# MCU.net
KiCad netlist of a schematic drawn in Altium Designer
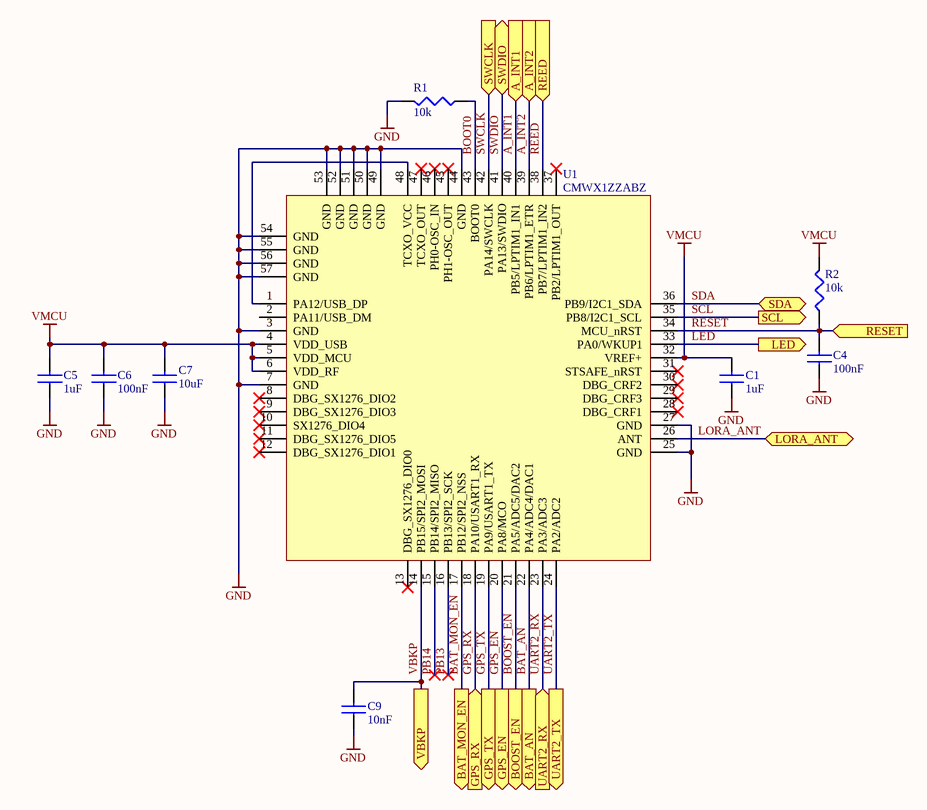
[diagram p0: MCU.SchDoc]

(export (version "E")
  (design (tool "Eeschema 10.0.6"))
  (components
    (comp (ref "C1")
      (value "1uF")
      (footprint "CAP0402")
      (description "CAP CER 1UF 10V 20% X5R 0402")
      (fields
        (field (name "MANUFACTURER") "Murata")
        (field (name "MANUFACTURER PART NUMBER") "GRM155R61A105ME15D")
      )
      (libsource (lib "Passive") (part "C - 1uF/0402"))
    )
    (comp (ref "C4")
      (value "100nF")
      (footprint "CAP0402")
      (fields
        (field (name "MANUFACTURER") "Multicomp")
        (field (name "MANUFACTURER PART NUMBER") "MC0402X104J160CT")
        (field (name "TOLERANCE") "5%")
      )
      (libsource (lib "Passive") (part "C - 100nF/0402"))
    )
    (comp (ref "C5")
      (value "1uF")
      (footprint "CAP0402")
      (description "CAP CER 1UF 10V 20% X5R 0402")
      (fields
        (field (name "MANUFACTURER") "Murata")
        (field (name "MANUFACTURER PART NUMBER") "GRM155R61A105ME15D")
      )
      (libsource (lib "Passive") (part "C - 1uF/0402"))
    )
    (comp (ref "C6")
      (value "100nF")
      (footprint "CAP0402")
      (fields
        (field (name "MANUFACTURER") "Multicomp")
        (field (name "MANUFACTURER PART NUMBER") "MC0402X104J160CT")
        (field (name "TOLERANCE") "5%")
      )
      (libsource (lib "Passive") (part "C - 100nF/0402"))
    )
    (comp (ref "C7")
      (value "10uF")
      (footprint "CAP0603")
      (description "10uf/0603/20%")
      (fields
        (field (name "MANUFACTURER") "KEMET")
        (field (name "MANUFACTURER PART NUMBER") "C0603C106M8PACTU")
      )
      (libsource (lib "pira-smart-schlib") (part "10uF"))
    )
    (comp (ref "C9")
      (value "10nF")
      (footprint "CAP0402")
      (description "CAP CER 10000PF 16V X7R 0402")
      (fields
        (field (name "MANUFACTURER") "Murata")
        (field (name "MANUFACTURER PART NUMBER") "GRM155R71C103KA01D")
      )
      (libsource (lib "Passive") (part "C - 10nF/0402"))
    )
    (comp (ref "R1")
      (value "10k")
      (footprint "RES0402")
      (fields
        (field (name "MANUFACTURER") "Multicomp")
        (field (name "MANUFACTURER PART NUMBER") "MCWR04X1002FTL")
        (field (name "TOLERANCE") "1%")
      )
      (libsource (lib "Passive") (part "R - 10k/0402"))
    )
    (comp (ref "R2")
      (value "10k")
      (footprint "RES0402")
      (fields
        (field (name "MANUFACTURER") "Multicomp")
        (field (name "MANUFACTURER PART NUMBER") "MCWR04X1002FTL")
        (field (name "TOLERANCE") "1%")
      )
      (libsource (lib "Passive") (part "R - 10k/0402"))
    )
    (comp (ref "U1")
      (value "CMWX1ZZABZ")
      (footprint "Lora Module ES0")
      (description "RF Module, FSK, OOK, LoRa, 4.8Kbps, 915MHz, -135.5dBm, 2.2V to 3.6V, I2C, SPI, UART, USB")
      (fields
        (field (name "MANUFACTURER") "Murata")
        (field (name "MANUFACTURER PART NUMBER") "CMWX1ZZABZ-091")
      )
      (libsource (lib "Active") (part "MCU - CMWX1ZZABZ"))
    )
  )
  (nets
    (net (code "1") (name "/A_INT1") (class "Default")
      (node (ref "U1") (pin "40") (pinfunction "PB5/LPTIM1_IN1_40") (pintype "passive"))
    )
    (net (code "2") (name "/A_INT2") (class "Default")
      (node (ref "U1") (pin "39") (pinfunction "PB6/LPTIM1_ETR_39") (pintype "passive"))
    )
    (net (code "3") (name "/BAT_AN") (class "Default")
      (node (ref "U1") (pin "22") (pinfunction "PA4/ADC4/DAC1_22") (pintype "passive"))
    )
    (net (code "4") (name "/BAT_MON_EN") (class "Default")
      (node (ref "U1") (pin "17") (pinfunction "PB12/SPI2_NSS_17") (pintype "passive"))
    )
    (net (code "5") (name "/BOOST_EN") (class "Default")
      (node (ref "U1") (pin "21") (pinfunction "PA5/ADC5/DAC2_21") (pintype "passive"))
    )
    (net (code "6") (name "/BOOT0") (class "Default")
      (node (ref "R1") (pin "1") (pinfunction "1_1") (pintype "passive"))
      (node (ref "U1") (pin "43") (pinfunction "BOOT0_43") (pintype "passive"))
    )
    (net (code "7") (name "/GPS_EN") (class "Default")
      (node (ref "U1") (pin "20") (pinfunction "PA8/MCO_20") (pintype "passive"))
    )
    (net (code "8") (name "/GPS_RX") (class "Default")
      (node (ref "U1") (pin "18") (pinfunction "PA10/USART1_RX_18") (pintype "passive"))
    )
    (net (code "9") (name "/GPS_TX") (class "Default")
      (node (ref "U1") (pin "19") (pinfunction "PA9/USART1_TX_19") (pintype "passive"))
    )
    (net (code "10") (name "/LED") (class "Default")
      (node (ref "U1") (pin "33") (pinfunction "PA0/WKUP1_33") (pintype "passive"))
    )
    (net (code "11") (name "/LORA_ANT") (class "Default")
      (node (ref "U1") (pin "26") (pinfunction "ANT_26") (pintype "passive"))
    )
    (net (code "12") (name "/PB13") (class "Default")
      (node (ref "U1") (pin "16") (pinfunction "PB13/SPI2_SCK_16") (pintype "passive+no_connect"))
    )
    (net (code "13") (name "/PB14") (class "Default")
      (node (ref "U1") (pin "15") (pinfunction "PB14/SPI2_MISO_15") (pintype "passive+no_connect"))
    )
    (net (code "14") (name "/REED") (class "Default")
      (node (ref "U1") (pin "38") (pinfunction "PB7/LPTIM1_IN2_38") (pintype "passive"))
    )
    (net (code "15") (name "/RESET") (class "Default")
      (node (ref "C4") (pin "2") (pinfunction "2_2") (pintype "passive"))
      (node (ref "R2") (pin "1") (pinfunction "1_1") (pintype "passive"))
      (node (ref "U1") (pin "34") (pinfunction "MCU_nRST_34") (pintype "passive"))
    )
    (net (code "16") (name "/SCL") (class "Default")
      (node (ref "U1") (pin "35") (pinfunction "PB8/I2C1_SCL_35") (pintype "passive"))
    )
    (net (code "17") (name "/SDA") (class "Default")
      (node (ref "U1") (pin "36") (pinfunction "PB9/I2C1_SDA_36") (pintype "passive"))
    )
    (net (code "18") (name "/SWCLK") (class "Default")
      (node (ref "U1") (pin "42") (pinfunction "PA14/SWCLK_42") (pintype "passive"))
    )
    (net (code "19") (name "/SWDIO") (class "Default")
      (node (ref "U1") (pin "41") (pinfunction "PA13/SWDIO_41") (pintype "passive"))
    )
    (net (code "20") (name "/UART2_RX") (class "Default")
      (node (ref "U1") (pin "23") (pinfunction "PA3/ADC3_23") (pintype "passive"))
    )
    (net (code "21") (name "/UART2_TX") (class "Default")
      (node (ref "U1") (pin "24") (pinfunction "PA2/ADC2_24") (pintype "passive"))
    )
    (net (code "22") (name "/VBKP") (class "Default")
      (node (ref "C9") (pin "2") (pinfunction "2_2") (pintype "passive"))
      (node (ref "U1") (pin "14") (pinfunction "PB15/SPI2_MOSI_14") (pintype "passive"))
    )
    (net (code "23") (name "GND") (class "Default")
      (node (ref "C1") (pin "1") (pinfunction "1_1") (pintype "passive"))
      (node (ref "C4") (pin "1") (pinfunction "1_1") (pintype "passive"))
      (node (ref "C5") (pin "1") (pinfunction "1_1") (pintype "passive"))
      (node (ref "C6") (pin "1") (pinfunction "1_1") (pintype "passive"))
      (node (ref "C7") (pin "1") (pinfunction "1_1") (pintype "passive"))
      (node (ref "C9") (pin "1") (pinfunction "1_1") (pintype "passive"))
      (node (ref "R1") (pin "2") (pinfunction "2_2") (pintype "passive"))
      (node (ref "U1") (pin "25") (pinfunction "GND_25") (pintype "passive"))
      (node (ref "U1") (pin "27") (pinfunction "GND_27") (pintype "passive"))
      (node (ref "U1") (pin "3") (pinfunction "GND_3") (pintype "passive"))
      (node (ref "U1") (pin "44") (pinfunction "GND_44") (pintype "passive"))
      (node (ref "U1") (pin "49") (pinfunction "GND_49") (pintype "passive"))
      (node (ref "U1") (pin "50") (pinfunction "GND_50") (pintype "passive"))
      (node (ref "U1") (pin "51") (pinfunction "GND_51") (pintype "passive"))
      (node (ref "U1") (pin "52") (pinfunction "GND_52") (pintype "passive"))
      (node (ref "U1") (pin "53") (pinfunction "GND_53") (pintype "passive"))
      (node (ref "U1") (pin "54") (pinfunction "GND_54") (pintype "passive"))
      (node (ref "U1") (pin "55") (pinfunction "GND_55") (pintype "passive"))
      (node (ref "U1") (pin "56") (pinfunction "GND_56") (pintype "passive"))
      (node (ref "U1") (pin "57") (pinfunction "GND_57") (pintype "passive"))
      (node (ref "U1") (pin "7") (pinfunction "GND_7") (pintype "passive"))
    )
    (net (code "24") (name "Net-(U1-PA12{slash}USB_DP)") (class "Default")
      (node (ref "U1") (pin "1") (pinfunction "PA12/USB_DP_1") (pintype "passive"))
      (node (ref "U1") (pin "48") (pinfunction "TCXO_VCC_48") (pintype "passive"))
    )
    (net (code "25") (name "VMCU") (class "Default")
      (node (ref "C1") (pin "2") (pinfunction "2_2") (pintype "passive"))
      (node (ref "C5") (pin "2") (pinfunction "2_2") (pintype "passive"))
      (node (ref "C6") (pin "2") (pinfunction "2_2") (pintype "passive"))
      (node (ref "C7") (pin "2") (pinfunction "2_2") (pintype "passive"))
      (node (ref "R2") (pin "2") (pinfunction "2_2") (pintype "passive"))
      (node (ref "U1") (pin "32") (pinfunction "VREF+_32") (pintype "passive"))
      (node (ref "U1") (pin "4") (pinfunction "VDD_USB_4") (pintype "passive"))
      (node (ref "U1") (pin "5") (pinfunction "VDD_MCU_5") (pintype "passive"))
      (node (ref "U1") (pin "6") (pinfunction "VDD_RF_6") (pintype "passive"))
    )
    (net (code "26") (name "unconnected-(U1-DBG_CRF1-Pad28)") (class "Default")
      (node (ref "U1") (pin "28") (pinfunction "DBG_CRF1_28") (pintype "passive+no_connect"))
    )
    (net (code "27") (name "unconnected-(U1-DBG_CRF2-Pad30)") (class "Default")
      (node (ref "U1") (pin "30") (pinfunction "DBG_CRF2_30") (pintype "passive+no_connect"))
    )
    (net (code "28") (name "unconnected-(U1-DBG_CRF3-Pad29)") (class "Default")
      (node (ref "U1") (pin "29") (pinfunction "DBG_CRF3_29") (pintype "passive+no_connect"))
    )
    (net (code "29") (name "unconnected-(U1-DBG_SX1276_DIO0-Pad13)") (class "Default")
      (node (ref "U1") (pin "13") (pinfunction "DBG_SX1276_DIO0_13") (pintype "passive+no_connect"))
    )
    (net (code "30") (name "unconnected-(U1-DBG_SX1276_DIO1-Pad12)") (class "Default")
      (node (ref "U1") (pin "12") (pinfunction "DBG_SX1276_DIO1_12") (pintype "passive+no_connect"))
    )
    (net (code "31") (name "unconnected-(U1-DBG_SX1276_DIO2-Pad8)") (class "Default")
      (node (ref "U1") (pin "8") (pinfunction "DBG_SX1276_DIO2_8") (pintype "passive+no_connect"))
    )
    (net (code "32") (name "unconnected-(U1-DBG_SX1276_DIO3-Pad9)") (class "Default")
      (node (ref "U1") (pin "9") (pinfunction "DBG_SX1276_DIO3_9") (pintype "passive+no_connect"))
    )
    (net (code "33") (name "unconnected-(U1-DBG_SX1276_DIO5-Pad11)") (class "Default")
      (node (ref "U1") (pin "11") (pinfunction "DBG_SX1276_DIO5_11") (pintype "passive+no_connect"))
    )
    (net (code "34") (name "unconnected-(U1-PA11{slash}USB_DM-Pad2)") (class "Default")
      (node (ref "U1") (pin "2") (pinfunction "PA11/USB_DM_2") (pintype "passive"))
    )
    (net (code "35") (name "unconnected-(U1-PB2{slash}LPTIM1_OUT-Pad37)") (class "Default")
      (node (ref "U1") (pin "37") (pinfunction "PB2/LPTIM1_OUT_37") (pintype "passive+no_connect"))
    )
    (net (code "36") (name "unconnected-(U1-PH0-OSC_IN-Pad46)") (class "Default")
      (node (ref "U1") (pin "46") (pinfunction "PH0-OSC_IN_46") (pintype "passive+no_connect"))
    )
    (net (code "37") (name "unconnected-(U1-PH1-OSC_OUT-Pad45)") (class "Default")
      (node (ref "U1") (pin "45") (pinfunction "PH1-OSC_OUT_45") (pintype "passive+no_connect"))
    )
    (net (code "38") (name "unconnected-(U1-STSAFE_nRST-Pad31)") (class "Default")
      (node (ref "U1") (pin "31") (pinfunction "STSAFE_nRST_31") (pintype "passive+no_connect"))
    )
    (net (code "39") (name "unconnected-(U1-SX1276_DIO4-Pad10)") (class "Default")
      (node (ref "U1") (pin "10") (pinfunction "SX1276_DIO4_10") (pintype "passive+no_connect"))
    )
    (net (code "40") (name "unconnected-(U1-TCXO_OUT-Pad47)") (class "Default")
      (node (ref "U1") (pin "47") (pinfunction "TCXO_OUT_47") (pintype "passive+no_connect"))
    )
  )
)
